# Sht12-V12P0_reg.net
KiCad netlist of a schematic drawn in Altium Designer
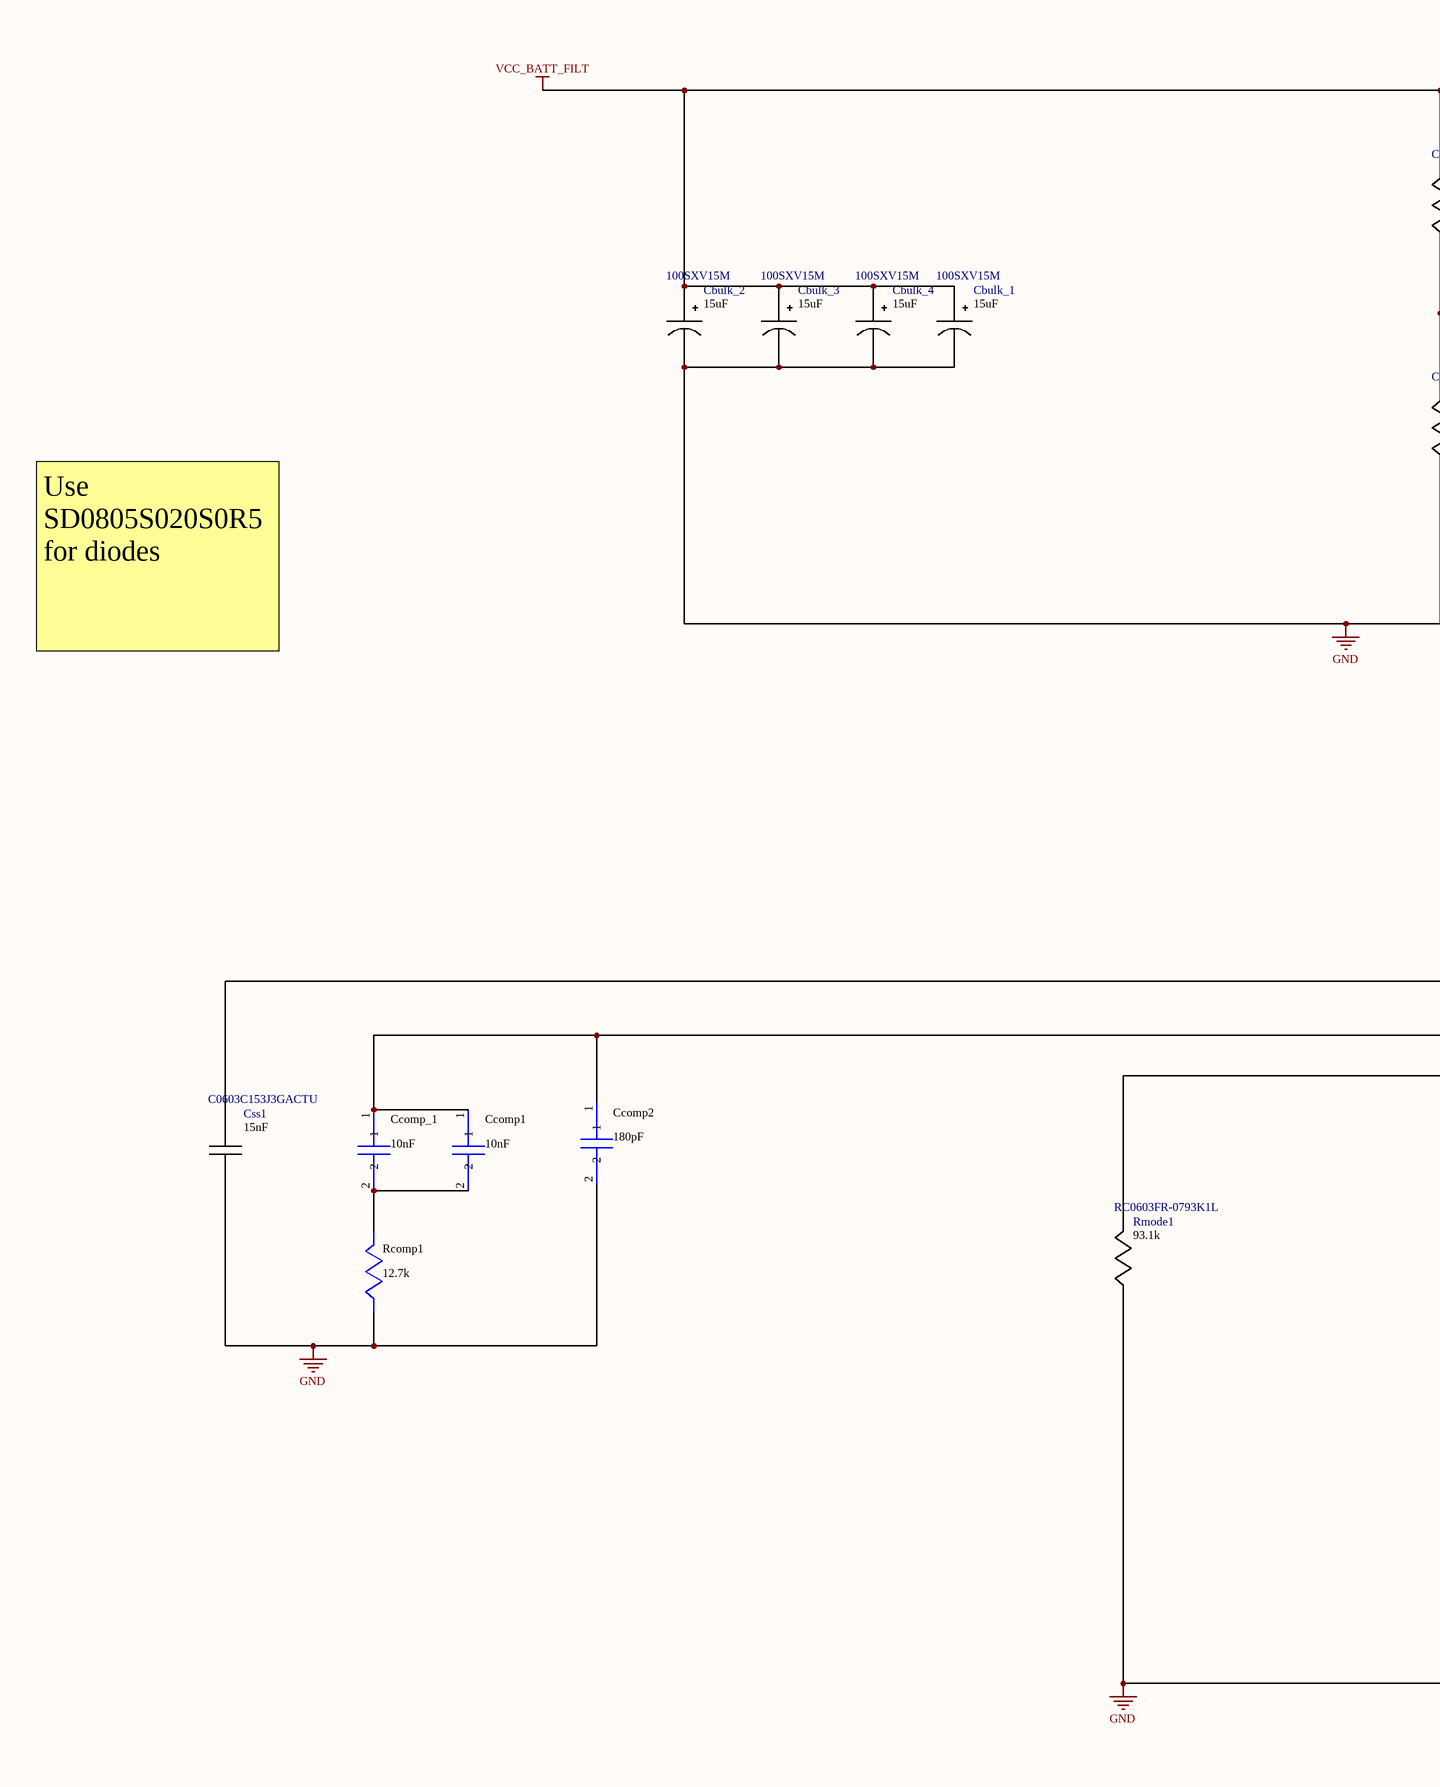
[diagram p0: Sht12-V12P0_reg.SchDoc, left]
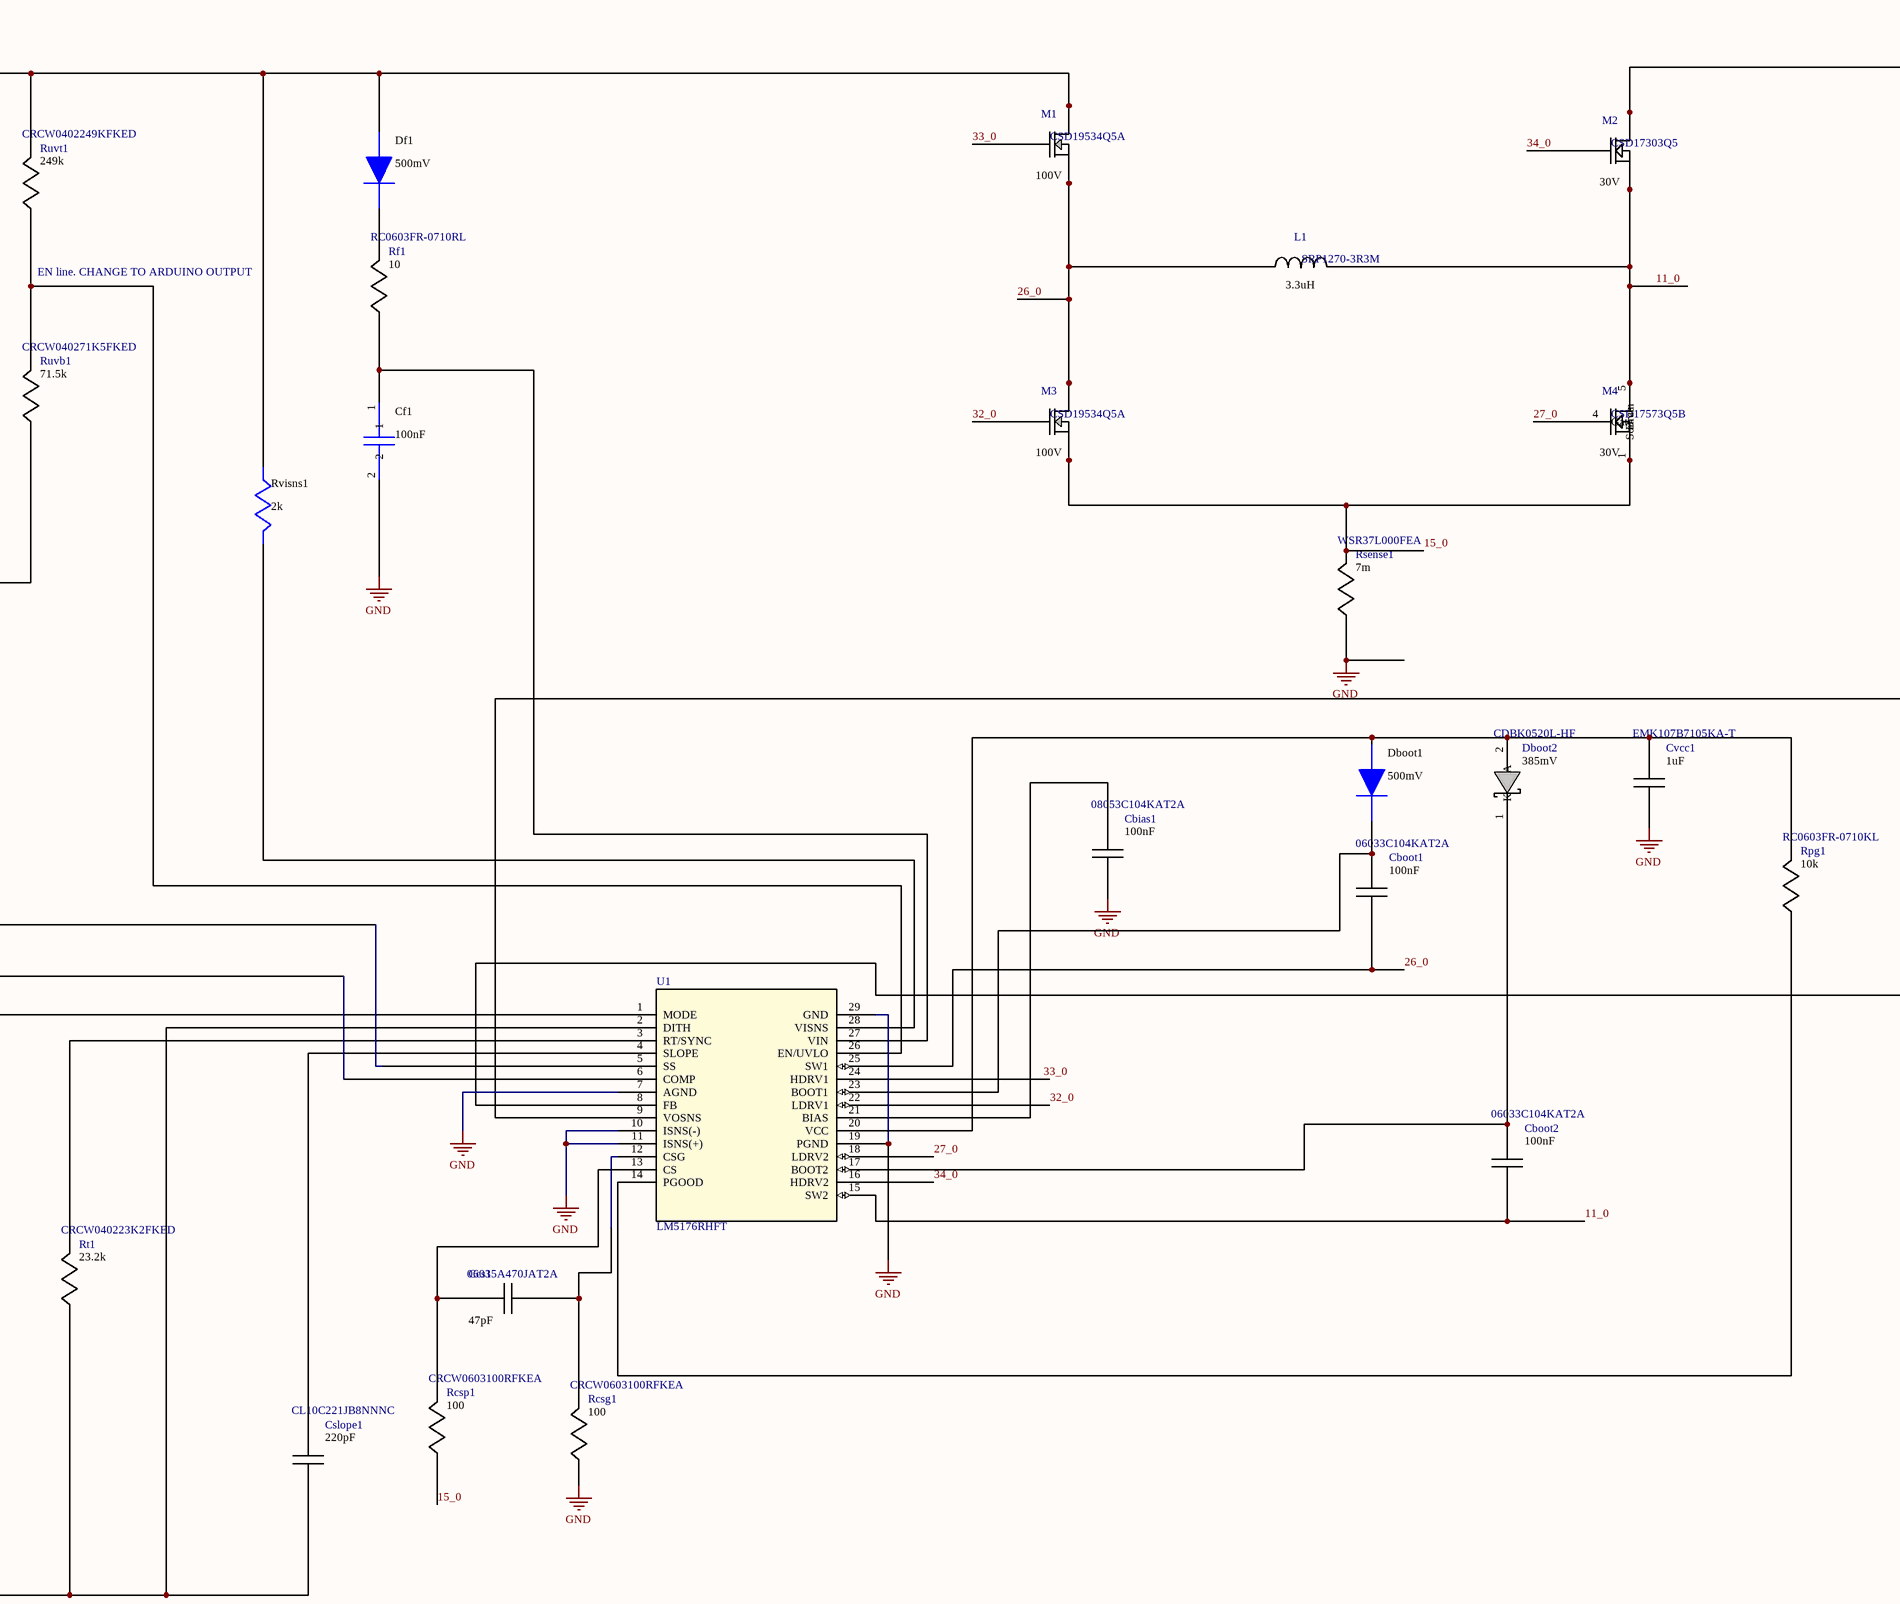
[diagram p1: Sht12-V12P0_reg.SchDoc, middle]
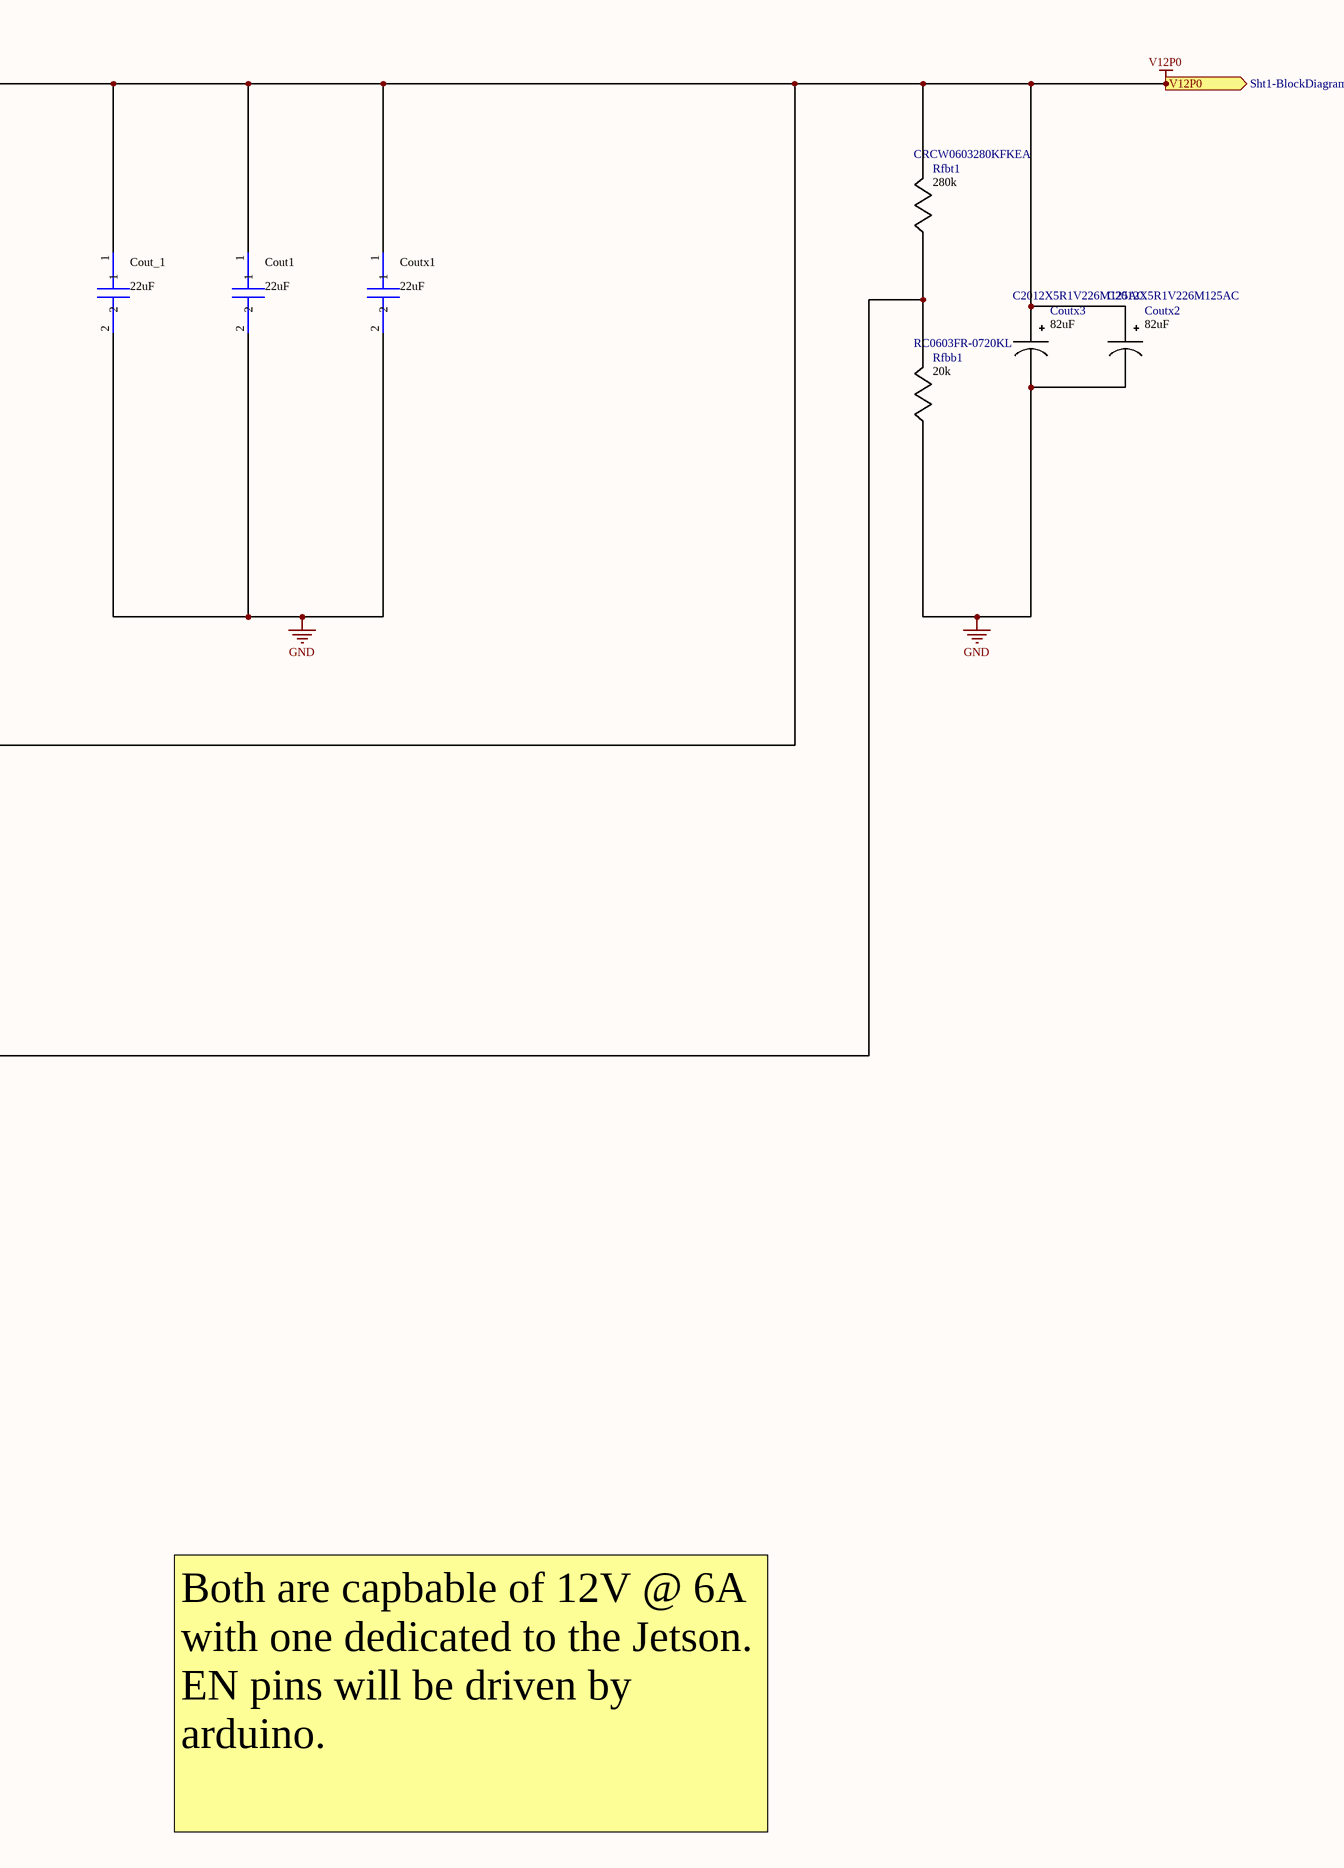
[diagram p2: Sht12-V12P0_reg.SchDoc, right]

(export (version "E")
  (design (tool "Eeschema 10.0.6"))
  (components
    (comp (ref "Cbias1")
      (value "08053C104KAT2A")
      (footprint "0805")
      (fields (field (name "ALTIUM_VALUE") "100nF"))
      (libsource (lib "TAUV-Lib") (part "08053C104KAT2A"))
    )
    (comp (ref "Cboot1")
      (value "06033C104KAT2A")
      (footprint "0603")
      (fields (field (name "ALTIUM_VALUE") "100nF"))
      (libsource (lib "TAUV-Lib") (part "06033C104KAT2A"))
    )
    (comp (ref "Cboot2")
      (value "06033C104KAT2A")
      (footprint "0603")
      (fields (field (name "ALTIUM_VALUE") "100nF"))
      (libsource (lib "TAUV-Lib") (part "06033C104KAT2A"))
    )
    (comp (ref "Cbulk_1")
      (value "100SXV15M")
      (footprint "CAPSMT_62_E12")
      (fields (field (name "ALTIUM_VALUE") "15uF"))
      (libsource (lib "TAUV-Lib") (part "100SXV15M"))
    )
    (comp (ref "Cbulk_2")
      (value "100SXV15M")
      (footprint "CAPSMT_62_E12")
      (fields (field (name "ALTIUM_VALUE") "15uF"))
      (libsource (lib "TAUV-Lib") (part "100SXV15M"))
    )
    (comp (ref "Cbulk_3")
      (value "100SXV15M")
      (footprint "CAPSMT_62_E12")
      (fields (field (name "ALTIUM_VALUE") "15uF"))
      (libsource (lib "TAUV-Lib") (part "100SXV15M"))
    )
    (comp (ref "Cbulk_4")
      (value "100SXV15M")
      (footprint "CAPSMT_62_E12")
      (fields (field (name "ALTIUM_VALUE") "15uF"))
      (libsource (lib "TAUV-Lib") (part "100SXV15M"))
    )
    (comp (ref "Ccomp1")
      (value "10nF")
      (footprint "0805")
      (description "CGA2B3X7R1H103K0")
      (fields
        (field (name "MANUFACTURER PART NUMBER") "CGA2B3X7R1H103K050BB")
        (field (name "Comment") "C0805C181K5GACTU")
      )
      (libsource (lib "TAUV-Lib") (part "Ccomp_2"))
    )
    (comp (ref "Ccomp2")
      (value "180pF")
      (footprint "0402")
      (description "C0805C181K5GACTU")
      (fields (field (name "Comment") "CGA2B3X7R1H103K050BB"))
      (libsource (lib "TAUV-Lib") (part "Ccomp2"))
    )
    (comp (ref "Ccomp_1")
      (value "10nF")
      (footprint "0402")
      (description "CGA2B3X7R1H103K0")
      (fields (field (name "MANUFACTURER PART NUMBER") "CGA2B3X7R1H103K050BB"))
      (libsource (lib "TAUV-Lib") (part "Ccomp"))
    )
    (comp (ref "Ccs1")
      (value "06035A470JAT2A")
      (footprint "0603")
      (fields (field (name "ALTIUM_VALUE") "47pF"))
      (libsource (lib "TAUV-Lib") (part "06035A470JAT2A"))
    )
    (comp (ref "Cf1")
      (value "100nF")
      (footprint "0603")
      (description "CGA3E2X7R1H104K0")
      (fields (field (name "MANUFACTURER PART NUMBER") "CGA3E2X7R1H104K080AA"))
      (libsource (lib "TAUV-Lib") (part "Cf"))
    )
    (comp (ref "Cout1")
      (value "22uF")
      (footprint "CAPSMT_62_E61")
      (description "C2012X5R1V226M12")
      (fields
        (field (name "MANUFACTURER PART NUMBER") "C2012X5R1V226M125AC")
        (field (name "Comment") "16SVPF82M")
      )
      (libsource (lib "TAUV-Lib") (part "Coutx2"))
    )
    (comp (ref "Coutx1")
      (value "22uF")
      (footprint "0805")
      (description "C2012X5R1V226M12")
      (fields (field (name "MANUFACTURER PART NUMBER") "C2012X5R1V226M125AC"))
      (libsource (lib "TAUV-Lib") (part "Coutx3"))
    )
    (comp (ref "Coutx2")
      (value "C2012X5R1V226M125AC")
      (footprint "0805")
      (description "16SVPF82M")
      (fields (field (name "ALTIUM_VALUE") "82uF"))
      (libsource (lib "TAUV-Lib") (part "16SVPF82M"))
    )
    (comp (ref "Coutx3")
      (value "C2012X5R1V226M125AC")
      (footprint "0805")
      (description "16SVPF82M")
      (fields (field (name "ALTIUM_VALUE") "82uF"))
      (libsource (lib "TAUV-Lib") (part "16SVPF82M"))
    )
    (comp (ref "Cout_1")
      (value "22uF")
      (footprint "CAPSMT_62_E61")
      (description "C2012X5R1V226M12")
      (fields
        (field (name "MANUFACTURER PART NUMBER") "C2012X5R1V226M125AC")
        (field (name "Comment") "16SVPF82M")
      )
      (libsource (lib "TAUV-Lib") (part "Coutx"))
    )
    (comp (ref "Cslope1")
      (value "CL10C221JB8NNNC")
      (footprint "0603")
      (fields (field (name "ALTIUM_VALUE") "220pF"))
      (libsource (lib "TAUV-Lib") (part "CL10C221JB8NNNC"))
    )
    (comp (ref "Css1")
      (value "C0603C153J3GACTU")
      (footprint "0603")
      (fields (field (name "ALTIUM_VALUE") "15nF"))
      (libsource (lib "TAUV-Lib") (part "C0603C153J3GACTU"))
    )
    (comp (ref "Cvcc1")
      (value "EMK107B7105KA-T")
      (footprint "0603")
      (fields (field (name "ALTIUM_VALUE") "1uF"))
      (libsource (lib "TAUV-Lib") (part "EMK107B7105KA-T"))
    )
    (comp (ref "Dboot1")
      (value "500mV")
      (footprint "GEN_Diode")
      (description "CUSTOM1")
      (fields (field (name "MANUFACTURER PART NUMBER") "GENERIC_DIODE"))
      (libsource (lib "TAUV-Lib") (part "Dboot1"))
    )
    (comp (ref "Dboot2")
      (value "CDBK0520L-HF")
      (footprint "SOD-123F")
      (fields (field (name "ALTIUM_VALUE") "385mV"))
      (libsource (lib "TAUV-Lib") (part "CDBK0520L-HF"))
    )
    (comp (ref "Df1")
      (value "500mV")
      (footprint "GEN_Diode")
      (description "CUSTOM2")
      (fields (field (name "MANUFACTURER PART NUMBER") "GENERIC_DIODE"))
      (libsource (lib "TAUV-Lib") (part "Df"))
    )
    (comp (ref "L1")
      (value "SRP1270-3R3M")
      (footprint "SRP1270")
      (fields (field (name "ALTIUM_VALUE") "3.3uH"))
      (libsource (lib "TAUV-Lib") (part "SRP1270-3R3M"))
    )
    (comp (ref "M1")
      (value "CSD19534Q5A")
      (footprint "TRANS_NexFET_Q5A")
      (fields (field (name "ALTIUM_VALUE") "100V"))
      (libsource (lib "TAUV-Lib") (part "CSD19534Q5A"))
    )
    (comp (ref "M2")
      (value "CSD17303Q5")
      (footprint "TRANS_NexFET_Q5")
      (fields (field (name "ALTIUM_VALUE") "30V"))
      (libsource (lib "TAUV-Lib") (part "CSD17303Q5"))
    )
    (comp (ref "M3")
      (value "CSD19534Q5A")
      (footprint "TRANS_NexFET_Q5A")
      (fields (field (name "ALTIUM_VALUE") "100V"))
      (libsource (lib "TAUV-Lib") (part "CSD19534Q5A"))
    )
    (comp (ref "M4")
      (value "CSD17573Q5B")
      (footprint "DNK0008A")
      (description "CSD17573Q5B- Note out of stock, double check available subs")
      (fields (field (name "ALTIUM_VALUE") "30V"))
      (libsource (lib "TAUV-Lib") (part "CSD17573Q5B"))
    )
    (comp (ref "Rcomp1")
      (value "12.7k")
      (footprint "0402")
      (description "CRCW040212K7FKED")
      (libsource (lib "TAUV-Lib") (part "Rcomp"))
    )
    (comp (ref "Rcsg1")
      (value "CRCW0603100RFKEA")
      (footprint "0603")
      (fields (field (name "ALTIUM_VALUE") "100"))
      (libsource (lib "TAUV-Lib") (part "CRCW0603100RFKEA"))
    )
    (comp (ref "Rcsp1")
      (value "CRCW0603100RFKEA")
      (footprint "0603")
      (fields (field (name "ALTIUM_VALUE") "100"))
      (libsource (lib "TAUV-Lib") (part "CRCW0603100RFKEA"))
    )
    (comp (ref "Rf1")
      (value "RC0603FR-0710RL")
      (footprint "0603")
      (fields (field (name "ALTIUM_VALUE") "10"))
      (libsource (lib "TAUV-Lib") (part "RC0603FR-0710RL"))
    )
    (comp (ref "Rfbb1")
      (value "RC0603FR-0720KL")
      (footprint "0603")
      (fields (field (name "ALTIUM_VALUE") "20k"))
      (libsource (lib "TAUV-Lib") (part "RC0603FR-0720KL"))
    )
    (comp (ref "Rfbt1")
      (value "CRCW0603280KFKEA")
      (footprint "0603")
      (fields (field (name "ALTIUM_VALUE") "280k"))
      (libsource (lib "TAUV-Lib") (part "CRCW0603280KFKEA"))
    )
    (comp (ref "Rmode1")
      (value "RC0603FR-0793K1L")
      (footprint "0603")
      (fields (field (name "ALTIUM_VALUE") "93.1k"))
      (libsource (lib "TAUV-Lib") (part "RC0603FR-0793K1L"))
    )
    (comp (ref "Rpg1")
      (value "RC0603FR-0710KL")
      (footprint "0603")
      (fields (field (name "ALTIUM_VALUE") "10k"))
      (libsource (lib "TAUV-Lib") (part "RC0603FR-0710KL"))
    )
    (comp (ref "Rsense1")
      (value "WSR37L000FEA")
      (footprint "4527")
      (fields (field (name "ALTIUM_VALUE") "7m"))
      (libsource (lib "TAUV-Lib") (part "WSR37L000FEA"))
    )
    (comp (ref "Rt1")
      (value "CRCW040223K2FKED")
      (footprint "0402")
      (fields (field (name "ALTIUM_VALUE") "23.2k"))
      (libsource (lib "TAUV-Lib") (part "CRCW040223K2FKED"))
    )
    (comp (ref "Ruvb1")
      (value "CRCW040271K5FKED")
      (footprint "0402")
      (fields (field (name "ALTIUM_VALUE") "71.5k"))
      (libsource (lib "TAUV-Lib") (part "CRCW040271K5FKED"))
    )
    (comp (ref "Ruvt1")
      (value "CRCW0402249KFKED")
      (footprint "0402")
      (fields (field (name "ALTIUM_VALUE") "249k"))
      (libsource (lib "TAUV-Lib") (part "CRCW0402249KFKED"))
    )
    (comp (ref "Rvisns1")
      (value "2k")
      (footprint "0603")
      (description "CRCW06032K00FKEA")
      (libsource (lib "TAUV-Lib") (part "Rvisns"))
    )
    (comp (ref "U1")
      (value "LM5176RHFT")
      (footprint "VQFN_76RHFT_TEX")
      (description "No Description Available")
      (fields (field (name "COPYRIGHT") "Copyright (C) 2022 Ultra Librarian. All rights reserved."))
      (libsource (lib "TAUV-Lib") (part "LM5176RHFT"))
    )
  )
  (nets
    (net (code "1") (name "/11_0") (class "Default")
      (node (ref "Cboot2") (pin "2") (pinfunction "2_2") (pintype "passive"))
      (node (ref "L1") (pin "2") (pinfunction "2_2") (pintype "passive"))
      (node (ref "M2") (pin "1") (pinfunction "Source_1") (pintype "passive"))
      (node (ref "M2") (pin "2") (pinfunction "Source_2") (pintype "passive"))
      (node (ref "M2") (pin "3") (pinfunction "Source_3") (pintype "passive"))
      (node (ref "M4") (pin "5") (pinfunction "Drain_5") (pintype "passive"))
      (node (ref "M4") (pin "6") (pinfunction "Drain_6") (pintype "passive"))
      (node (ref "M4") (pin "7") (pinfunction "Drain_7") (pintype "passive"))
      (node (ref "M4") (pin "8") (pinfunction "Drain_8") (pintype "passive"))
      (node (ref "M4") (pin "9") (pinfunction "Drain_9") (pintype "passive"))
      (node (ref "U1") (pin "15") (pinfunction "SW2_15") (pintype "bidirectional"))
    )
    (net (code "2") (name "/15_0") (class "Default")
      (node (ref "M3") (pin "1") (pinfunction "Source_1") (pintype "passive"))
      (node (ref "M3") (pin "2") (pinfunction "Source_2") (pintype "passive"))
      (node (ref "M3") (pin "3") (pinfunction "Source_3") (pintype "passive"))
      (node (ref "M4") (pin "1") (pinfunction "Source_1") (pintype "passive"))
      (node (ref "M4") (pin "2") (pinfunction "Source_2") (pintype "passive"))
      (node (ref "M4") (pin "3") (pinfunction "Source_3") (pintype "passive"))
      (node (ref "Rcsp1") (pin "2") (pinfunction "2_2") (pintype "passive"))
      (node (ref "Rsense1") (pin "1") (pinfunction "1_1") (pintype "passive"))
    )
    (net (code "3") (name "/26_0") (class "Default")
      (node (ref "Cboot1") (pin "2") (pinfunction "2_2") (pintype "passive"))
      (node (ref "L1") (pin "1") (pinfunction "1_1") (pintype "passive"))
      (node (ref "M1") (pin "1") (pinfunction "Source_1") (pintype "passive"))
      (node (ref "M1") (pin "2") (pinfunction "Source_2") (pintype "passive"))
      (node (ref "M1") (pin "3") (pinfunction "Source_3") (pintype "passive"))
      (node (ref "M3") (pin "5") (pinfunction "Drain_5") (pintype "passive"))
      (node (ref "M3") (pin "6") (pinfunction "Drain_6") (pintype "passive"))
      (node (ref "M3") (pin "7") (pinfunction "Drain_7") (pintype "passive"))
      (node (ref "M3") (pin "8") (pinfunction "Drain_8") (pintype "passive"))
      (node (ref "M3") (pin "9") (pinfunction "Drain_9") (pintype "passive"))
      (node (ref "U1") (pin "25") (pinfunction "SW1_25") (pintype "bidirectional"))
    )
    (net (code "4") (name "/27_0") (class "Default")
      (node (ref "M4") (pin "4") (pinfunction "Gate_4") (pintype "passive"))
      (node (ref "U1") (pin "18") (pinfunction "LDRV2_18") (pintype "bidirectional"))
    )
    (net (code "5") (name "/32_0") (class "Default")
      (node (ref "M3") (pin "4") (pinfunction "Gate_4") (pintype "passive"))
      (node (ref "U1") (pin "22") (pinfunction "LDRV1_22") (pintype "bidirectional"))
    )
    (net (code "6") (name "/33_0") (class "Default")
      (node (ref "M1") (pin "4") (pinfunction "Gate_4") (pintype "passive"))
      (node (ref "U1") (pin "24") (pinfunction "HDRV1_24") (pintype "passive"))
    )
    (net (code "7") (name "/34_0") (class "Default")
      (node (ref "M2") (pin "4") (pinfunction "Gate_4") (pintype "passive"))
      (node (ref "U1") (pin "16") (pinfunction "HDRV2_16") (pintype "passive"))
    )
    (net (code "8") (name "GND") (class "Default")
      (node (ref "Cbias1") (pin "2") (pinfunction "2_2") (pintype "passive"))
      (node (ref "Cbulk_1") (pin "2") (pinfunction "-_2") (pintype "passive"))
      (node (ref "Cbulk_2") (pin "2") (pinfunction "-_2") (pintype "passive"))
      (node (ref "Cbulk_3") (pin "2") (pinfunction "-_2") (pintype "passive"))
      (node (ref "Cbulk_4") (pin "2") (pinfunction "-_2") (pintype "passive"))
      (node (ref "Ccomp2") (pin "2") (pinfunction "2_2") (pintype "passive"))
      (node (ref "Cf1") (pin "2") (pinfunction "2_2") (pintype "passive"))
      (node (ref "Cout1") (pin "2") (pinfunction "2_2") (pintype "passive"))
      (node (ref "Cout_1") (pin "2") (pinfunction "2_2") (pintype "passive"))
      (node (ref "Coutx1") (pin "2") (pinfunction "2_2") (pintype "passive"))
      (node (ref "Coutx2") (pin "2") (pinfunction "-_2") (pintype "passive"))
      (node (ref "Coutx3") (pin "2") (pinfunction "-_2") (pintype "passive"))
      (node (ref "Cslope1") (pin "2") (pinfunction "2_2") (pintype "passive"))
      (node (ref "Css1") (pin "2") (pinfunction "2_2") (pintype "passive"))
      (node (ref "Cvcc1") (pin "2") (pinfunction "2_2") (pintype "passive"))
      (node (ref "Rcomp1") (pin "2") (pinfunction "2_2") (pintype "passive"))
      (node (ref "Rcsg1") (pin "2") (pinfunction "2_2") (pintype "passive"))
      (node (ref "Rfbb1") (pin "2") (pinfunction "2_2") (pintype "passive"))
      (node (ref "Rmode1") (pin "2") (pinfunction "2_2") (pintype "passive"))
      (node (ref "Rsense1") (pin "2") (pinfunction "2_2") (pintype "passive"))
      (node (ref "Rt1") (pin "2") (pinfunction "2_2") (pintype "passive"))
      (node (ref "Ruvb1") (pin "2") (pinfunction "2_2") (pintype "passive"))
      (node (ref "U1") (pin "10") (pinfunction "ISNS(-)_10") (pintype "passive"))
      (node (ref "U1") (pin "11") (pinfunction "ISNS(+)_11") (pintype "passive"))
      (node (ref "U1") (pin "19") (pinfunction "PGND_19") (pintype "passive"))
      (node (ref "U1") (pin "2") (pinfunction "DITH_2") (pintype "passive"))
      (node (ref "U1") (pin "29") (pinfunction "GND_29") (pintype "passive"))
      (node (ref "U1") (pin "7") (pinfunction "AGND_7") (pintype "passive"))
    )
    (net (code "9") (name "Net-(Ccomp1-Pad2)") (class "Default")
      (node (ref "Ccomp1") (pin "2") (pinfunction "2_2") (pintype "passive"))
      (node (ref "Ccomp_1") (pin "2") (pinfunction "2_2") (pintype "passive"))
      (node (ref "Rcomp1") (pin "1") (pinfunction "1_1") (pintype "passive"))
    )
    (net (code "10") (name "Net-(Dboot1-A)") (class "Default")
      (node (ref "Cvcc1") (pin "1") (pinfunction "1_1") (pintype "passive"))
      (node (ref "Dboot1") (pin "2") (pinfunction "A_2") (pintype "passive"))
      (node (ref "Dboot2") (pin "2") (pinfunction "A_2") (pintype "passive"))
      (node (ref "Rpg1") (pin "1") (pinfunction "1_1") (pintype "passive"))
      (node (ref "U1") (pin "20") (pinfunction "VCC_20") (pintype "power_in"))
    )
    (net (code "11") (name "Net-(Dboot1-K)") (class "Default")
      (node (ref "Cboot1") (pin "1") (pinfunction "1_1") (pintype "passive"))
      (node (ref "Dboot1") (pin "1") (pinfunction "K_1") (pintype "passive"))
      (node (ref "U1") (pin "23") (pinfunction "BOOT1_23") (pintype "bidirectional"))
    )
    (net (code "12") (name "Net-(Dboot2-K)") (class "Default")
      (node (ref "Cboot2") (pin "1") (pinfunction "1_1") (pintype "passive"))
      (node (ref "Dboot2") (pin "1") (pinfunction "K_1") (pintype "passive"))
      (node (ref "U1") (pin "17") (pinfunction "BOOT2_17") (pintype "bidirectional"))
    )
    (net (code "13") (name "Net-(Df1-K)") (class "Default")
      (node (ref "Df1") (pin "1") (pinfunction "K_1") (pintype "passive"))
      (node (ref "Rf1") (pin "1") (pinfunction "1_1") (pintype "passive"))
    )
    (net (code "14") (name "Net-(U1-BIAS)") (class "Default")
      (node (ref "Cbias1") (pin "1") (pinfunction "1_1") (pintype "passive"))
      (node (ref "U1") (pin "21") (pinfunction "BIAS_21") (pintype "passive"))
    )
    (net (code "15") (name "Net-(U1-COMP)") (class "Default")
      (node (ref "Ccomp1") (pin "1") (pinfunction "1_1") (pintype "passive"))
      (node (ref "Ccomp2") (pin "1") (pinfunction "1_1") (pintype "passive"))
      (node (ref "Ccomp_1") (pin "1") (pinfunction "1_1") (pintype "passive"))
      (node (ref "U1") (pin "6") (pinfunction "COMP_6") (pintype "passive"))
    )
    (net (code "16") (name "Net-(U1-CS)") (class "Default")
      (node (ref "Ccs1") (pin "1") (pinfunction "1_1") (pintype "passive"))
      (node (ref "Rcsp1") (pin "1") (pinfunction "1_1") (pintype "passive"))
      (node (ref "U1") (pin "13") (pinfunction "CS_13") (pintype "passive"))
    )
    (net (code "17") (name "Net-(U1-CSG)") (class "Default")
      (node (ref "Ccs1") (pin "2") (pinfunction "2_2") (pintype "passive"))
      (node (ref "Rcsg1") (pin "1") (pinfunction "1_1") (pintype "passive"))
      (node (ref "U1") (pin "12") (pinfunction "CSG_12") (pintype "passive"))
    )
    (net (code "18") (name "Net-(U1-EN{slash}UVLO)") (class "Default")
      (node (ref "Ruvb1") (pin "1") (pinfunction "1_1") (pintype "passive"))
      (node (ref "Ruvt1") (pin "2") (pinfunction "2_2") (pintype "passive"))
      (node (ref "U1") (pin "26") (pinfunction "EN/UVLO_26") (pintype "passive"))
    )
    (net (code "19") (name "Net-(U1-FB)") (class "Default")
      (node (ref "Rfbb1") (pin "1") (pinfunction "1_1") (pintype "passive"))
      (node (ref "Rfbt1") (pin "2") (pinfunction "2_2") (pintype "passive"))
      (node (ref "U1") (pin "8") (pinfunction "FB_8") (pintype "passive"))
    )
    (net (code "20") (name "Net-(U1-MODE)") (class "Default")
      (node (ref "Rmode1") (pin "1") (pinfunction "1_1") (pintype "passive"))
      (node (ref "U1") (pin "1") (pinfunction "MODE_1") (pintype "passive"))
    )
    (net (code "21") (name "Net-(U1-PGOOD)") (class "Default")
      (node (ref "Rpg1") (pin "2") (pinfunction "2_2") (pintype "passive"))
      (node (ref "U1") (pin "14") (pinfunction "PGOOD_14") (pintype "power_in"))
    )
    (net (code "22") (name "Net-(U1-RT{slash}SYNC)") (class "Default")
      (node (ref "Rt1") (pin "1") (pinfunction "1_1") (pintype "passive"))
      (node (ref "U1") (pin "3") (pinfunction "RT/SYNC_3") (pintype "passive"))
    )
    (net (code "23") (name "Net-(U1-SLOPE)") (class "Default")
      (node (ref "Cslope1") (pin "1") (pinfunction "1_1") (pintype "passive"))
      (node (ref "U1") (pin "4") (pinfunction "SLOPE_4") (pintype "passive"))
    )
    (net (code "24") (name "Net-(U1-SS)") (class "Default")
      (node (ref "Css1") (pin "1") (pinfunction "1_1") (pintype "passive"))
      (node (ref "U1") (pin "5") (pinfunction "SS_5") (pintype "passive"))
    )
    (net (code "25") (name "Net-(U1-VIN)") (class "Default")
      (node (ref "Cf1") (pin "1") (pinfunction "1_1") (pintype "passive"))
      (node (ref "Rf1") (pin "2") (pinfunction "2_2") (pintype "passive"))
      (node (ref "U1") (pin "27") (pinfunction "VIN_27") (pintype "passive"))
    )
    (net (code "26") (name "Net-(U1-VISNS)") (class "Default")
      (node (ref "Rvisns1") (pin "1") (pinfunction "1_1") (pintype "passive"))
      (node (ref "U1") (pin "28") (pinfunction "VISNS_28") (pintype "passive"))
    )
    (net (code "27") (name "V12P0") (class "Default")
      (node (ref "Cout1") (pin "1") (pinfunction "1_1") (pintype "passive"))
      (node (ref "Cout_1") (pin "1") (pinfunction "1_1") (pintype "passive"))
      (node (ref "Coutx1") (pin "1") (pinfunction "1_1") (pintype "passive"))
      (node (ref "Coutx2") (pin "1") (pinfunction "+_1") (pintype "passive"))
      (node (ref "Coutx3") (pin "1") (pinfunction "+_1") (pintype "passive"))
      (node (ref "M2") (pin "5") (pinfunction "Drain_5") (pintype "passive"))
      (node (ref "M2") (pin "6") (pinfunction "Drain_6") (pintype "passive"))
      (node (ref "M2") (pin "7") (pinfunction "Drain_7") (pintype "passive"))
      (node (ref "M2") (pin "8") (pinfunction "Drain_8") (pintype "passive"))
      (node (ref "M2") (pin "9") (pinfunction "Drain_9") (pintype "passive"))
      (node (ref "Rfbt1") (pin "1") (pinfunction "1_1") (pintype "passive"))
      (node (ref "U1") (pin "9") (pinfunction "VOSNS_9") (pintype "passive"))
    )
    (net (code "28") (name "VCC_BATT_FILT") (class "Default")
      (node (ref "Cbulk_1") (pin "1") (pinfunction "+_1") (pintype "passive"))
      (node (ref "Cbulk_2") (pin "1") (pinfunction "+_1") (pintype "passive"))
      (node (ref "Cbulk_3") (pin "1") (pinfunction "+_1") (pintype "passive"))
      (node (ref "Cbulk_4") (pin "1") (pinfunction "+_1") (pintype "passive"))
      (node (ref "Df1") (pin "2") (pinfunction "A_2") (pintype "passive"))
      (node (ref "M1") (pin "5") (pinfunction "Drain_5") (pintype "passive"))
      (node (ref "M1") (pin "6") (pinfunction "Drain_6") (pintype "passive"))
      (node (ref "M1") (pin "7") (pinfunction "Drain_7") (pintype "passive"))
      (node (ref "M1") (pin "8") (pinfunction "Drain_8") (pintype "passive"))
      (node (ref "M1") (pin "9") (pinfunction "Drain_9") (pintype "passive"))
      (node (ref "Ruvt1") (pin "1") (pinfunction "1_1") (pintype "passive"))
      (node (ref "Rvisns1") (pin "2") (pinfunction "2_2") (pintype "passive"))
    )
  )
)
